# MCH_FPGA_GND_NC.net
KiCad netlist of a schematic drawn in Altium Designer
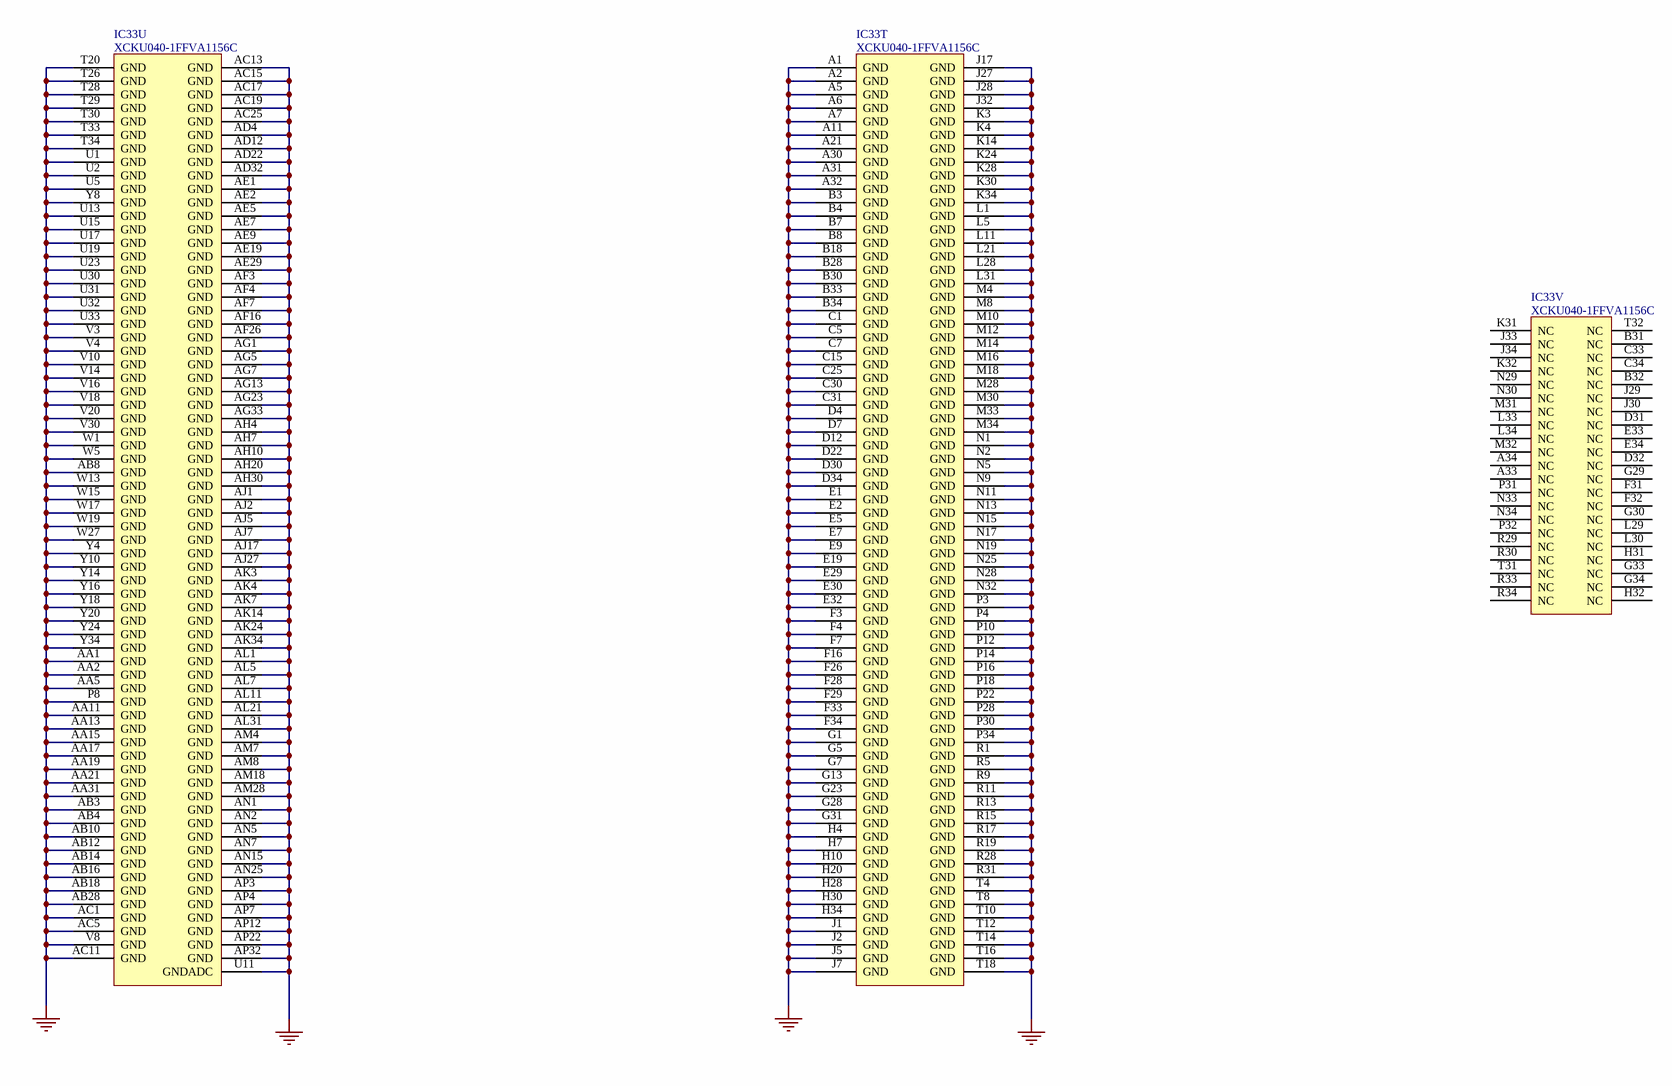
[diagram p0: MCH_FPGA_GND_NC.SchDoc]

(export (version "E")
  (design (tool "Eeschema 10.0.6"))
  (components
    (comp (ref "IC33")
      (value "XCKU040-1FFVA1156C")
      (footprint "BGA1156C100P34X34_3500X3500X350")
      (description "Kintex UltraScale FPGA, 520 I/O, 530K Cells, 1156-Ball BGA, Speed Grade 1, Commercial Grade")
      (fields (field (name "MANUFACTURER") "XILINX") (field (name "AUTHOR") "CERN DEM CA"))
      (libsource (lib "ICs And Semiconductors") (part "XCKU040-1FFVA1156C"))
    )
  )
  (nets
    (net (code "1") (name "GND") (class "Default")
      (node (ref "IC33") (pin "A1") (pinfunction "GND_A1") (pintype "power_in"))
      (node (ref "IC33") (pin "A11") (pinfunction "GND_A11") (pintype "power_in"))
      (node (ref "IC33") (pin "A2") (pinfunction "GND_A2") (pintype "power_in"))
      (node (ref "IC33") (pin "A21") (pinfunction "GND_A21") (pintype "power_in"))
      (node (ref "IC33") (pin "A30") (pinfunction "GND_A30") (pintype "power_in"))
      (node (ref "IC33") (pin "A31") (pinfunction "GND_A31") (pintype "power_in"))
      (node (ref "IC33") (pin "A32") (pinfunction "GND_A32") (pintype "power_in"))
      (node (ref "IC33") (pin "A5") (pinfunction "GND_A5") (pintype "power_in"))
      (node (ref "IC33") (pin "A6") (pinfunction "GND_A6") (pintype "power_in"))
      (node (ref "IC33") (pin "A7") (pinfunction "GND_A7") (pintype "power_in"))
      (node (ref "IC33") (pin "AA1") (pinfunction "GND_AA1") (pintype "power_in"))
      (node (ref "IC33") (pin "AA11") (pinfunction "GND_AA11") (pintype "power_in"))
      (node (ref "IC33") (pin "AA13") (pinfunction "GND_AA13") (pintype "power_in"))
      (node (ref "IC33") (pin "AA15") (pinfunction "GND_AA15") (pintype "power_in"))
      (node (ref "IC33") (pin "AA17") (pinfunction "GND_AA17") (pintype "power_in"))
      (node (ref "IC33") (pin "AA19") (pinfunction "GND_AA19") (pintype "power_in"))
      (node (ref "IC33") (pin "AA2") (pinfunction "GND_AA2") (pintype "power_in"))
      (node (ref "IC33") (pin "AA21") (pinfunction "GND_AA21") (pintype "power_in"))
      (node (ref "IC33") (pin "AA31") (pinfunction "GND_AA31") (pintype "power_in"))
      (node (ref "IC33") (pin "AA5") (pinfunction "GND_AA5") (pintype "power_in"))
      (node (ref "IC33") (pin "AB10") (pinfunction "GND_AB10") (pintype "power_in"))
      (node (ref "IC33") (pin "AB12") (pinfunction "GND_AB12") (pintype "power_in"))
      (node (ref "IC33") (pin "AB14") (pinfunction "GND_AB14") (pintype "power_in"))
      (node (ref "IC33") (pin "AB16") (pinfunction "GND_AB16") (pintype "power_in"))
      (node (ref "IC33") (pin "AB18") (pinfunction "GND_AB18") (pintype "power_in"))
      (node (ref "IC33") (pin "AB28") (pinfunction "GND_AB28") (pintype "power_in"))
      (node (ref "IC33") (pin "AB3") (pinfunction "GND_AB3") (pintype "power_in"))
      (node (ref "IC33") (pin "AB4") (pinfunction "GND_AB4") (pintype "power_in"))
      (node (ref "IC33") (pin "AB8") (pinfunction "GND_AB8") (pintype "power_in"))
      (node (ref "IC33") (pin "AC1") (pinfunction "GND_AC1") (pintype "power_in"))
      (node (ref "IC33") (pin "AC11") (pinfunction "GND_AC11") (pintype "power_in"))
      (node (ref "IC33") (pin "AC13") (pinfunction "GND_AC13") (pintype "power_in"))
      (node (ref "IC33") (pin "AC15") (pinfunction "GND_AC15") (pintype "power_in"))
      (node (ref "IC33") (pin "AC17") (pinfunction "GND_AC17") (pintype "power_in"))
      (node (ref "IC33") (pin "AC19") (pinfunction "GND_AC19") (pintype "power_in"))
      (node (ref "IC33") (pin "AC25") (pinfunction "GND_AC25") (pintype "power_in"))
      (node (ref "IC33") (pin "AC5") (pinfunction "GND_AC5") (pintype "power_in"))
      (node (ref "IC33") (pin "AD12") (pinfunction "GND_AD12") (pintype "power_in"))
      (node (ref "IC33") (pin "AD22") (pinfunction "GND_AD22") (pintype "power_in"))
      (node (ref "IC33") (pin "AD32") (pinfunction "GND_AD32") (pintype "power_in"))
      (node (ref "IC33") (pin "AD4") (pinfunction "GND_AD4") (pintype "power_in"))
      (node (ref "IC33") (pin "AE1") (pinfunction "GND_AE1") (pintype "power_in"))
      (node (ref "IC33") (pin "AE19") (pinfunction "GND_AE19") (pintype "power_in"))
      (node (ref "IC33") (pin "AE2") (pinfunction "GND_AE2") (pintype "power_in"))
      (node (ref "IC33") (pin "AE29") (pinfunction "GND_AE29") (pintype "power_in"))
      (node (ref "IC33") (pin "AE5") (pinfunction "GND_AE5") (pintype "power_in"))
      (node (ref "IC33") (pin "AE7") (pinfunction "GND_AE7") (pintype "power_in"))
      (node (ref "IC33") (pin "AE9") (pinfunction "GND_AE9") (pintype "power_in"))
      (node (ref "IC33") (pin "AF16") (pinfunction "GND_AF16") (pintype "power_in"))
      (node (ref "IC33") (pin "AF26") (pinfunction "GND_AF26") (pintype "power_in"))
      (node (ref "IC33") (pin "AF3") (pinfunction "GND_AF3") (pintype "power_in"))
      (node (ref "IC33") (pin "AF4") (pinfunction "GND_AF4") (pintype "power_in"))
      (node (ref "IC33") (pin "AF7") (pinfunction "GND_AF7") (pintype "power_in"))
      (node (ref "IC33") (pin "AG1") (pinfunction "GND_AG1") (pintype "power_in"))
      (node (ref "IC33") (pin "AG13") (pinfunction "GND_AG13") (pintype "power_in"))
      (node (ref "IC33") (pin "AG23") (pinfunction "GND_AG23") (pintype "power_in"))
      (node (ref "IC33") (pin "AG33") (pinfunction "GND_AG33") (pintype "power_in"))
      (node (ref "IC33") (pin "AG5") (pinfunction "GND_AG5") (pintype "power_in"))
      (node (ref "IC33") (pin "AG7") (pinfunction "GND_AG7") (pintype "power_in"))
      (node (ref "IC33") (pin "AH10") (pinfunction "GND_AH10") (pintype "power_in"))
      (node (ref "IC33") (pin "AH20") (pinfunction "GND_AH20") (pintype "power_in"))
      (node (ref "IC33") (pin "AH30") (pinfunction "GND_AH30") (pintype "power_in"))
      (node (ref "IC33") (pin "AH4") (pinfunction "GND_AH4") (pintype "power_in"))
      (node (ref "IC33") (pin "AH7") (pinfunction "GND_AH7") (pintype "power_in"))
      (node (ref "IC33") (pin "AJ1") (pinfunction "GND_AJ1") (pintype "power_in"))
      (node (ref "IC33") (pin "AJ17") (pinfunction "GND_AJ17") (pintype "power_in"))
      (node (ref "IC33") (pin "AJ2") (pinfunction "GND_AJ2") (pintype "power_in"))
      (node (ref "IC33") (pin "AJ27") (pinfunction "GND_AJ27") (pintype "power_in"))
      (node (ref "IC33") (pin "AJ5") (pinfunction "GND_AJ5") (pintype "power_in"))
      (node (ref "IC33") (pin "AJ7") (pinfunction "GND_AJ7") (pintype "power_in"))
      (node (ref "IC33") (pin "AK14") (pinfunction "GND_AK14") (pintype "power_in"))
      (node (ref "IC33") (pin "AK24") (pinfunction "GND_AK24") (pintype "power_in"))
      (node (ref "IC33") (pin "AK3") (pinfunction "GND_AK3") (pintype "power_in"))
      (node (ref "IC33") (pin "AK34") (pinfunction "GND_AK34") (pintype "power_in"))
      (node (ref "IC33") (pin "AK4") (pinfunction "GND_AK4") (pintype "power_in"))
      (node (ref "IC33") (pin "AK7") (pinfunction "GND_AK7") (pintype "power_in"))
      (node (ref "IC33") (pin "AL1") (pinfunction "GND_AL1") (pintype "power_in"))
      (node (ref "IC33") (pin "AL11") (pinfunction "GND_AL11") (pintype "power_in"))
      (node (ref "IC33") (pin "AL21") (pinfunction "GND_AL21") (pintype "power_in"))
      (node (ref "IC33") (pin "AL31") (pinfunction "GND_AL31") (pintype "power_in"))
      (node (ref "IC33") (pin "AL5") (pinfunction "GND_AL5") (pintype "power_in"))
      (node (ref "IC33") (pin "AL7") (pinfunction "GND_AL7") (pintype "power_in"))
      (node (ref "IC33") (pin "AM18") (pinfunction "GND_AM18") (pintype "power_in"))
      (node (ref "IC33") (pin "AM28") (pinfunction "GND_AM28") (pintype "power_in"))
      (node (ref "IC33") (pin "AM4") (pinfunction "GND_AM4") (pintype "power_in"))
      (node (ref "IC33") (pin "AM7") (pinfunction "GND_AM7") (pintype "power_in"))
      (node (ref "IC33") (pin "AM8") (pinfunction "GND_AM8") (pintype "power_in"))
      (node (ref "IC33") (pin "AN1") (pinfunction "GND_AN1") (pintype "power_in"))
      (node (ref "IC33") (pin "AN15") (pinfunction "GND_AN15") (pintype "power_in"))
      (node (ref "IC33") (pin "AN2") (pinfunction "GND_AN2") (pintype "power_in"))
      (node (ref "IC33") (pin "AN25") (pinfunction "GND_AN25") (pintype "power_in"))
      (node (ref "IC33") (pin "AN5") (pinfunction "GND_AN5") (pintype "power_in"))
      (node (ref "IC33") (pin "AN7") (pinfunction "GND_AN7") (pintype "power_in"))
      (node (ref "IC33") (pin "AP12") (pinfunction "GND_AP12") (pintype "power_in"))
      (node (ref "IC33") (pin "AP22") (pinfunction "GND_AP22") (pintype "power_in"))
      (node (ref "IC33") (pin "AP3") (pinfunction "GND_AP3") (pintype "power_in"))
      (node (ref "IC33") (pin "AP32") (pinfunction "GND_AP32") (pintype "power_in"))
      (node (ref "IC33") (pin "AP4") (pinfunction "GND_AP4") (pintype "power_in"))
      (node (ref "IC33") (pin "AP7") (pinfunction "GND_AP7") (pintype "power_in"))
      (node (ref "IC33") (pin "B18") (pinfunction "GND_B18") (pintype "power_in"))
      (node (ref "IC33") (pin "B28") (pinfunction "GND_B28") (pintype "power_in"))
      (node (ref "IC33") (pin "B3") (pinfunction "GND_B3") (pintype "power_in"))
      (node (ref "IC33") (pin "B30") (pinfunction "GND_B30") (pintype "power_in"))
      (node (ref "IC33") (pin "B33") (pinfunction "GND_B33") (pintype "power_in"))
      (node (ref "IC33") (pin "B34") (pinfunction "GND_B34") (pintype "power_in"))
      (node (ref "IC33") (pin "B4") (pinfunction "GND_B4") (pintype "power_in"))
      (node (ref "IC33") (pin "B7") (pinfunction "GND_B7") (pintype "power_in"))
      (node (ref "IC33") (pin "B8") (pinfunction "GND_B8") (pintype "power_in"))
      (node (ref "IC33") (pin "C1") (pinfunction "GND_C1") (pintype "power_in"))
      (node (ref "IC33") (pin "C15") (pinfunction "GND_C15") (pintype "power_in"))
      (node (ref "IC33") (pin "C25") (pinfunction "GND_C25") (pintype "power_in"))
      (node (ref "IC33") (pin "C30") (pinfunction "GND_C30") (pintype "power_in"))
      (node (ref "IC33") (pin "C31") (pinfunction "GND_C31") (pintype "power_in"))
      (node (ref "IC33") (pin "C5") (pinfunction "GND_C5") (pintype "power_in"))
      (node (ref "IC33") (pin "C7") (pinfunction "GND_C7") (pintype "power_in"))
      (node (ref "IC33") (pin "D12") (pinfunction "GND_D12") (pintype "power_in"))
      (node (ref "IC33") (pin "D22") (pinfunction "GND_D22") (pintype "power_in"))
      (node (ref "IC33") (pin "D30") (pinfunction "GND_D30") (pintype "power_in"))
      (node (ref "IC33") (pin "D34") (pinfunction "GND_D34") (pintype "power_in"))
      (node (ref "IC33") (pin "D4") (pinfunction "GND_D4") (pintype "power_in"))
      (node (ref "IC33") (pin "D7") (pinfunction "GND_D7") (pintype "power_in"))
      (node (ref "IC33") (pin "E1") (pinfunction "GND_E1") (pintype "power_in"))
      (node (ref "IC33") (pin "E19") (pinfunction "GND_E19") (pintype "power_in"))
      (node (ref "IC33") (pin "E2") (pinfunction "GND_E2") (pintype "power_in"))
      (node (ref "IC33") (pin "E29") (pinfunction "GND_E29") (pintype "power_in"))
      (node (ref "IC33") (pin "E30") (pinfunction "GND_E30") (pintype "power_in"))
      (node (ref "IC33") (pin "E32") (pinfunction "GND_E32") (pintype "power_in"))
      (node (ref "IC33") (pin "E5") (pinfunction "GND_E5") (pintype "power_in"))
      (node (ref "IC33") (pin "E7") (pinfunction "GND_E7") (pintype "power_in"))
      (node (ref "IC33") (pin "E9") (pinfunction "GND_E9") (pintype "power_in"))
      (node (ref "IC33") (pin "F16") (pinfunction "GND_F16") (pintype "power_in"))
      (node (ref "IC33") (pin "F26") (pinfunction "GND_F26") (pintype "power_in"))
      (node (ref "IC33") (pin "F28") (pinfunction "GND_F28") (pintype "power_in"))
      (node (ref "IC33") (pin "F29") (pinfunction "GND_F29") (pintype "power_in"))
      (node (ref "IC33") (pin "F3") (pinfunction "GND_F3") (pintype "power_in"))
      (node (ref "IC33") (pin "F33") (pinfunction "GND_F33") (pintype "power_in"))
      (node (ref "IC33") (pin "F34") (pinfunction "GND_F34") (pintype "power_in"))
      (node (ref "IC33") (pin "F4") (pinfunction "GND_F4") (pintype "power_in"))
      (node (ref "IC33") (pin "F7") (pinfunction "GND_F7") (pintype "power_in"))
      (node (ref "IC33") (pin "G1") (pinfunction "GND_G1") (pintype "power_in"))
      (node (ref "IC33") (pin "G13") (pinfunction "GND_G13") (pintype "power_in"))
      (node (ref "IC33") (pin "G23") (pinfunction "GND_G23") (pintype "power_in"))
      (node (ref "IC33") (pin "G28") (pinfunction "GND_G28") (pintype "power_in"))
      (node (ref "IC33") (pin "G31") (pinfunction "GND_G31") (pintype "power_in"))
      (node (ref "IC33") (pin "G5") (pinfunction "GND_G5") (pintype "power_in"))
      (node (ref "IC33") (pin "G7") (pinfunction "GND_G7") (pintype "power_in"))
      (node (ref "IC33") (pin "H10") (pinfunction "GND_H10") (pintype "power_in"))
      (node (ref "IC33") (pin "H20") (pinfunction "GND_H20") (pintype "power_in"))
      (node (ref "IC33") (pin "H28") (pinfunction "GND_H28") (pintype "power_in"))
      (node (ref "IC33") (pin "H30") (pinfunction "GND_H30") (pintype "power_in"))
      (node (ref "IC33") (pin "H34") (pinfunction "GND_H34") (pintype "power_in"))
      (node (ref "IC33") (pin "H4") (pinfunction "GND_H4") (pintype "power_in"))
      (node (ref "IC33") (pin "H7") (pinfunction "GND_H7") (pintype "power_in"))
      (node (ref "IC33") (pin "J1") (pinfunction "GND_J1") (pintype "power_in"))
      (node (ref "IC33") (pin "J17") (pinfunction "GND_J17") (pintype "power_in"))
      (node (ref "IC33") (pin "J2") (pinfunction "GND_J2") (pintype "power_in"))
      (node (ref "IC33") (pin "J27") (pinfunction "GND_J27") (pintype "power_in"))
      (node (ref "IC33") (pin "J28") (pinfunction "GND_J28") (pintype "power_in"))
      (node (ref "IC33") (pin "J32") (pinfunction "GND_J32") (pintype "power_in"))
      (node (ref "IC33") (pin "J5") (pinfunction "GND_J5") (pintype "power_in"))
      (node (ref "IC33") (pin "J7") (pinfunction "GND_J7") (pintype "power_in"))
      (node (ref "IC33") (pin "K14") (pinfunction "GND_K14") (pintype "power_in"))
      (node (ref "IC33") (pin "K24") (pinfunction "GND_K24") (pintype "power_in"))
      (node (ref "IC33") (pin "K28") (pinfunction "GND_K28") (pintype "power_in"))
      (node (ref "IC33") (pin "K3") (pinfunction "GND_K3") (pintype "power_in"))
      (node (ref "IC33") (pin "K30") (pinfunction "GND_K30") (pintype "power_in"))
      (node (ref "IC33") (pin "K34") (pinfunction "GND_K34") (pintype "power_in"))
      (node (ref "IC33") (pin "K4") (pinfunction "GND_K4") (pintype "power_in"))
      (node (ref "IC33") (pin "L1") (pinfunction "GND_L1") (pintype "power_in"))
      (node (ref "IC33") (pin "L11") (pinfunction "GND_L11") (pintype "power_in"))
      (node (ref "IC33") (pin "L21") (pinfunction "GND_L21") (pintype "power_in"))
      (node (ref "IC33") (pin "L28") (pinfunction "GND_L28") (pintype "power_in"))
      (node (ref "IC33") (pin "L31") (pinfunction "GND_L31") (pintype "power_in"))
      (node (ref "IC33") (pin "L5") (pinfunction "GND_L5") (pintype "power_in"))
      (node (ref "IC33") (pin "M10") (pinfunction "GND_M10") (pintype "power_in"))
      (node (ref "IC33") (pin "M12") (pinfunction "GND_M12") (pintype "power_in"))
      (node (ref "IC33") (pin "M14") (pinfunction "GND_M14") (pintype "power_in"))
      (node (ref "IC33") (pin "M16") (pinfunction "GND_M16") (pintype "power_in"))
      (node (ref "IC33") (pin "M18") (pinfunction "GND_M18") (pintype "power_in"))
      (node (ref "IC33") (pin "M28") (pinfunction "GND_M28") (pintype "power_in"))
      (node (ref "IC33") (pin "M30") (pinfunction "GND_M30") (pintype "power_in"))
      (node (ref "IC33") (pin "M33") (pinfunction "GND_M33") (pintype "power_in"))
      (node (ref "IC33") (pin "M34") (pinfunction "GND_M34") (pintype "power_in"))
      (node (ref "IC33") (pin "M4") (pinfunction "GND_M4") (pintype "power_in"))
      (node (ref "IC33") (pin "M8") (pinfunction "GND_M8") (pintype "power_in"))
      (node (ref "IC33") (pin "N1") (pinfunction "GND_N1") (pintype "power_in"))
      (node (ref "IC33") (pin "N11") (pinfunction "GND_N11") (pintype "power_in"))
      (node (ref "IC33") (pin "N13") (pinfunction "GND_N13") (pintype "power_in"))
      (node (ref "IC33") (pin "N15") (pinfunction "GND_N15") (pintype "power_in"))
      (node (ref "IC33") (pin "N17") (pinfunction "GND_N17") (pintype "power_in"))
      (node (ref "IC33") (pin "N19") (pinfunction "GND_N19") (pintype "power_in"))
      (node (ref "IC33") (pin "N2") (pinfunction "GND_N2") (pintype "power_in"))
      (node (ref "IC33") (pin "N25") (pinfunction "GND_N25") (pintype "power_in"))
      (node (ref "IC33") (pin "N28") (pinfunction "GND_N28") (pintype "power_in"))
      (node (ref "IC33") (pin "N32") (pinfunction "GND_N32") (pintype "power_in"))
      (node (ref "IC33") (pin "N5") (pinfunction "GND_N5") (pintype "power_in"))
      (node (ref "IC33") (pin "N9") (pinfunction "GND_N9") (pintype "power_in"))
      (node (ref "IC33") (pin "P10") (pinfunction "GND_P10") (pintype "power_in"))
      (node (ref "IC33") (pin "P12") (pinfunction "GND_P12") (pintype "power_in"))
      (node (ref "IC33") (pin "P14") (pinfunction "GND_P14") (pintype "power_in"))
      (node (ref "IC33") (pin "P16") (pinfunction "GND_P16") (pintype "power_in"))
      (node (ref "IC33") (pin "P18") (pinfunction "GND_P18") (pintype "power_in"))
      (node (ref "IC33") (pin "P22") (pinfunction "GND_P22") (pintype "power_in"))
      (node (ref "IC33") (pin "P28") (pinfunction "GND_P28") (pintype "power_in"))
      (node (ref "IC33") (pin "P3") (pinfunction "GND_P3") (pintype "power_in"))
      (node (ref "IC33") (pin "P30") (pinfunction "GND_P30") (pintype "power_in"))
      (node (ref "IC33") (pin "P34") (pinfunction "GND_P34") (pintype "power_in"))
      (node (ref "IC33") (pin "P4") (pinfunction "GND_P4") (pintype "power_in"))
      (node (ref "IC33") (pin "P8") (pinfunction "GND_P8") (pintype "power_in"))
      (node (ref "IC33") (pin "R1") (pinfunction "GND_R1") (pintype "power_in"))
      (node (ref "IC33") (pin "R11") (pinfunction "GND_R11") (pintype "power_in"))
      (node (ref "IC33") (pin "R13") (pinfunction "GND_R13") (pintype "power_in"))
      (node (ref "IC33") (pin "R15") (pinfunction "GND_R15") (pintype "power_in"))
      (node (ref "IC33") (pin "R17") (pinfunction "GND_R17") (pintype "power_in"))
      (node (ref "IC33") (pin "R19") (pinfunction "GND_R19") (pintype "power_in"))
      (node (ref "IC33") (pin "R28") (pinfunction "GND_R28") (pintype "power_in"))
      (node (ref "IC33") (pin "R31") (pinfunction "GND_R31") (pintype "power_in"))
      (node (ref "IC33") (pin "R5") (pinfunction "GND_R5") (pintype "power_in"))
      (node (ref "IC33") (pin "R9") (pinfunction "GND_R9") (pintype "power_in"))
      (node (ref "IC33") (pin "T10") (pinfunction "GND_T10") (pintype "power_in"))
      (node (ref "IC33") (pin "T12") (pinfunction "GND_T12") (pintype "power_in"))
      (node (ref "IC33") (pin "T14") (pinfunction "GND_T14") (pintype "power_in"))
      (node (ref "IC33") (pin "T16") (pinfunction "GND_T16") (pintype "power_in"))
      (node (ref "IC33") (pin "T18") (pinfunction "GND_T18") (pintype "power_in"))
      (node (ref "IC33") (pin "T20") (pinfunction "GND_T20") (pintype "power_in"))
      (node (ref "IC33") (pin "T26") (pinfunction "GND_T26") (pintype "power_in"))
      (node (ref "IC33") (pin "T28") (pinfunction "GND_T28") (pintype "power_in"))
      (node (ref "IC33") (pin "T29") (pinfunction "GND_T29") (pintype "power_in"))
      (node (ref "IC33") (pin "T30") (pinfunction "GND_T30") (pintype "power_in"))
      (node (ref "IC33") (pin "T33") (pinfunction "GND_T33") (pintype "power_in"))
      (node (ref "IC33") (pin "T34") (pinfunction "GND_T34") (pintype "power_in"))
      (node (ref "IC33") (pin "T4") (pinfunction "GND_T4") (pintype "power_in"))
      (node (ref "IC33") (pin "T8") (pinfunction "GND_T8") (pintype "power_in"))
      (node (ref "IC33") (pin "U1") (pinfunction "GND_U1") (pintype "power_in"))
      (node (ref "IC33") (pin "U11") (pinfunction "GNDADC_U11") (pintype "power_in"))
      (node (ref "IC33") (pin "U13") (pinfunction "GND_U13") (pintype "power_in"))
      (node (ref "IC33") (pin "U15") (pinfunction "GND_U15") (pintype "power_in"))
      (node (ref "IC33") (pin "U17") (pinfunction "GND_U17") (pintype "power_in"))
      (node (ref "IC33") (pin "U19") (pinfunction "GND_U19") (pintype "power_in"))
      (node (ref "IC33") (pin "U2") (pinfunction "GND_U2") (pintype "power_in"))
      (node (ref "IC33") (pin "U23") (pinfunction "GND_U23") (pintype "power_in"))
      (node (ref "IC33") (pin "U30") (pinfunction "GND_U30") (pintype "power_in"))
      (node (ref "IC33") (pin "U31") (pinfunction "GND_U31") (pintype "power_in"))
      (node (ref "IC33") (pin "U32") (pinfunction "GND_U32") (pintype "power_in"))
      (node (ref "IC33") (pin "U33") (pinfunction "GND_U33") (pintype "power_in"))
      (node (ref "IC33") (pin "U5") (pinfunction "GND_U5") (pintype "power_in"))
      (node (ref "IC33") (pin "V10") (pinfunction "GND_V10") (pintype "power_in"))
      (node (ref "IC33") (pin "V14") (pinfunction "GND_V14") (pintype "power_in"))
      (node (ref "IC33") (pin "V16") (pinfunction "GND_V16") (pintype "power_in"))
      (node (ref "IC33") (pin "V18") (pinfunction "GND_V18") (pintype "power_in"))
      (node (ref "IC33") (pin "V20") (pinfunction "GND_V20") (pintype "power_in"))
      (node (ref "IC33") (pin "V3") (pinfunction "GND_V3") (pintype "power_in"))
      (node (ref "IC33") (pin "V30") (pinfunction "GND_V30") (pintype "power_in"))
      (node (ref "IC33") (pin "V4") (pinfunction "GND_V4") (pintype "power_in"))
      (node (ref "IC33") (pin "V8") (pinfunction "GND_V8") (pintype "power_in"))
      (node (ref "IC33") (pin "W1") (pinfunction "GND_W1") (pintype "power_in"))
      (node (ref "IC33") (pin "W13") (pinfunction "GND_W13") (pintype "power_in"))
      (node (ref "IC33") (pin "W15") (pinfunction "GND_W15") (pintype "power_in"))
      (node (ref "IC33") (pin "W17") (pinfunction "GND_W17") (pintype "power_in"))
      (node (ref "IC33") (pin "W19") (pinfunction "GND_W19") (pintype "power_in"))
      (node (ref "IC33") (pin "W27") (pinfunction "GND_W27") (pintype "power_in"))
      (node (ref "IC33") (pin "W5") (pinfunction "GND_W5") (pintype "power_in"))
      (node (ref "IC33") (pin "Y10") (pinfunction "GND_Y10") (pintype "power_in"))
      (node (ref "IC33") (pin "Y14") (pinfunction "GND_Y14") (pintype "power_in"))
      (node (ref "IC33") (pin "Y16") (pinfunction "GND_Y16") (pintype "power_in"))
      (node (ref "IC33") (pin "Y18") (pinfunction "GND_Y18") (pintype "power_in"))
      (node (ref "IC33") (pin "Y20") (pinfunction "GND_Y20") (pintype "power_in"))
      (node (ref "IC33") (pin "Y24") (pinfunction "GND_Y24") (pintype "power_in"))
      (node (ref "IC33") (pin "Y34") (pinfunction "GND_Y34") (pintype "power_in"))
      (node (ref "IC33") (pin "Y4") (pinfunction "GND_Y4") (pintype "power_in"))
      (node (ref "IC33") (pin "Y8") (pinfunction "GND_Y8") (pintype "power_in"))
    )
    (net (code "2") (name "unconnected-(IC33V-NC-PadA33)") (class "Default")
      (node (ref "IC33") (pin "A33") (pinfunction "NC_A33") (pintype "passive"))
    )
    (net (code "3") (name "unconnected-(IC33V-NC-PadA34)") (class "Default")
      (node (ref "IC33") (pin "A34") (pinfunction "NC_A34") (pintype "passive"))
    )
    (net (code "4") (name "unconnected-(IC33V-NC-PadB31)") (class "Default")
      (node (ref "IC33") (pin "B31") (pinfunction "NC_B31") (pintype "passive"))
    )
    (net (code "5") (name "unconnected-(IC33V-NC-PadB32)") (class "Default")
      (node (ref "IC33") (pin "B32") (pinfunction "NC_B32") (pintype "passive"))
    )
    (net (code "6") (name "unconnected-(IC33V-NC-PadC33)") (class "Default")
      (node (ref "IC33") (pin "C33") (pinfunction "NC_C33") (pintype "passive"))
    )
    (net (code "7") (name "unconnected-(IC33V-NC-PadC34)") (class "Default")
      (node (ref "IC33") (pin "C34") (pinfunction "NC_C34") (pintype "passive"))
    )
    (net (code "8") (name "unconnected-(IC33V-NC-PadD31)") (class "Default")
      (node (ref "IC33") (pin "D31") (pinfunction "NC_D31") (pintype "passive"))
    )
    (net (code "9") (name "unconnected-(IC33V-NC-PadD32)") (class "Default")
      (node (ref "IC33") (pin "D32") (pinfunction "NC_D32") (pintype "passive"))
    )
    (net (code "10") (name "unconnected-(IC33V-NC-PadE33)") (class "Default")
      (node (ref "IC33") (pin "E33") (pinfunction "NC_E33") (pintype "passive"))
    )
    (net (code "11") (name "unconnected-(IC33V-NC-PadE34)") (class "Default")
      (node (ref "IC33") (pin "E34") (pinfunction "NC_E34") (pintype "passive"))
    )
    (net (code "12") (name "unconnected-(IC33V-NC-PadF31)") (class "Default")
      (node (ref "IC33") (pin "F31") (pinfunction "NC_F31") (pintype "passive"))
    )
    (net (code "13") (name "unconnected-(IC33V-NC-PadF32)") (class "Default")
      (node (ref "IC33") (pin "F32") (pinfunction "NC_F32") (pintype "passive"))
    )
    (net (code "14") (name "unconnected-(IC33V-NC-PadG29)") (class "Default")
      (node (ref "IC33") (pin "G29") (pinfunction "NC_G29") (pintype "passive"))
    )
    (net (code "15") (name "unconnected-(IC33V-NC-PadG30)") (class "Default")
      (node (ref "IC33") (pin "G30") (pinfunction "NC_G30") (pintype "passive"))
    )
    (net (code "16") (name "unconnected-(IC33V-NC-PadG33)") (class "Default")
      (node (ref "IC33") (pin "G33") (pinfunction "NC_G33") (pintype "passive"))
    )
    (net (code "17") (name "unconnected-(IC33V-NC-PadG34)") (class "Default")
      (node (ref "IC33") (pin "G34") (pinfunction "NC_G34") (pintype "passive"))
    )
    (net (code "18") (name "unconnected-(IC33V-NC-PadH31)") (class "Default")
      (node (ref "IC33") (pin "H31") (pinfunction "NC_H31") (pintype "passive"))
    )
    (net (code "19") (name "unconnected-(IC33V-NC-PadH32)") (class "Default")
      (node (ref "IC33") (pin "H32") (pinfunction "NC_H32") (pintype "passive"))
    )
    (net (code "20") (name "unconnected-(IC33V-NC-PadJ29)") (class "Default")
      (node (ref "IC33") (pin "J29") (pinfunction "NC_J29") (pintype "passive"))
    )
    (net (code "21") (name "unconnected-(IC33V-NC-PadJ30)") (class "Default")
      (node (ref "IC33") (pin "J30") (pinfunction "NC_J30") (pintype "passive"))
    )
    (net (code "22") (name "unconnected-(IC33V-NC-PadJ33)") (class "Default")
      (node (ref "IC33") (pin "J33") (pinfunction "NC_J33") (pintype "passive"))
    )
    (net (code "23") (name "unconnected-(IC33V-NC-PadJ34)") (class "Default")
      (node (ref "IC33") (pin "J34") (pinfunction "NC_J34") (pintype "passive"))
    )
    (net (code "24") (name "unconnected-(IC33V-NC-PadK31)") (class "Default")
      (node (ref "IC33") (pin "K31") (pinfunction "NC_K31") (pintype "passive"))
    )
    (net (code "25") (name "unconnected-(IC33V-NC-PadK32)") (class "Default")
      (node (ref "IC33") (pin "K32") (pinfunction "NC_K32") (pintype "passive"))
    )
    (net (code "26") (name "unconnected-(IC33V-NC-PadL29)") (class "Default")
      (node (ref "IC33") (pin "L29") (pinfunction "NC_L29") (pintype "passive"))
    )
    (net (code "27") (name "unconnected-(IC33V-NC-PadL30)") (class "Default")
      (node (ref "IC33") (pin "L30") (pinfunction "NC_L30") (pintype "passive"))
    )
    (net (code "28") (name "unconnected-(IC33V-NC-PadL33)") (class "Default")
      (node (ref "IC33") (pin "L33") (pinfunction "NC_L33") (pintype "passive"))
    )
    (net (code "29") (name "unconnected-(IC33V-NC-PadL34)") (class "Default")
      (node (ref "IC33") (pin "L34") (pinfunction "NC_L34") (pintype "passive"))
    )
    (net (code "30") (name "unconnected-(IC33V-NC-PadM31)") (class "Default")
      (node (ref "IC33") (pin "M31") (pinfunction "NC_M31") (pintype "passive"))
    )
    (net (code "31") (name "unconnected-(IC33V-NC-PadM32)") (class "Default")
      (node (ref "IC33") (pin "M32") (pinfunction "NC_M32") (pintype "passive"))
    )
    (net (code "32") (name "unconnected-(IC33V-NC-PadN29)") (class "Default")
      (node (ref "IC33") (pin "N29") (pinfunction "NC_N29") (pintype "passive"))
    )
    (net (code "33") (name "unconnected-(IC33V-NC-PadN30)") (class "Default")
      (node (ref "IC33") (pin "N30") (pinfunction "NC_N30") (pintype "passive"))
    )
    (net (code "34") (name "unconnected-(IC33V-NC-PadN33)") (class "Default")
      (node (ref "IC33") (pin "N33") (pinfunction "NC_N33") (pintype "passive"))
    )
    (net (code "35") (name "unconnected-(IC33V-NC-PadN34)") (class "Default")
      (node (ref "IC33") (pin "N34") (pinfunction "NC_N34") (pintype "passive"))
    )
    (net (code "36") (name "unconnected-(IC33V-NC-PadP31)") (class "Default")
      (node (ref "IC33") (pin "P31") (pinfunction "NC_P31") (pintype "passive"))
    )
    (net (code "37") (name "unconnected-(IC33V-NC-PadP32)") (class "Default")
      (node (ref "IC33") (pin "P32") (pinfunction "NC_P32") (pintype "passive"))
    )
    (net (code "38") (name "unconnected-(IC33V-NC-PadR29)") (class "Default")
      (node (ref "IC33") (pin "R29") (pinfunction "NC_R29") (pintype "passive"))
    )
    (net (code "39") (name "unconnected-(IC33V-NC-PadR30)") (class "Default")
      (node (ref "IC33") (pin "R30") (pinfunction "NC_R30") (pintype "passive"))
    )
    (net (code "40") (name "unconnected-(IC33V-NC-PadR33)") (class "Default")
      (node (ref "IC33") (pin "R33") (pinfunction "NC_R33") (pintype "passive"))
    )
    (net (code "41") (name "unconnected-(IC33V-NC-PadR34)") (class "Default")
      (node (ref "IC33") (pin "R34") (pinfunction "NC_R34") (pintype "passive"))
    )
    (net (code "42") (name "unconnected-(IC33V-NC-PadT31)") (class "Default")
      (node (ref "IC33") (pin "T31") (pinfunction "NC_T31") (pintype "passive"))
    )
    (net (code "43") (name "unconnected-(IC33V-NC-PadT32)") (class "Default")
      (node (ref "IC33") (pin "T32") (pinfunction "NC_T32") (pintype "passive"))
    )
  )
)
